# airButtonSwitch.net
KiCad netlist of a schematic drawn in EAGLE
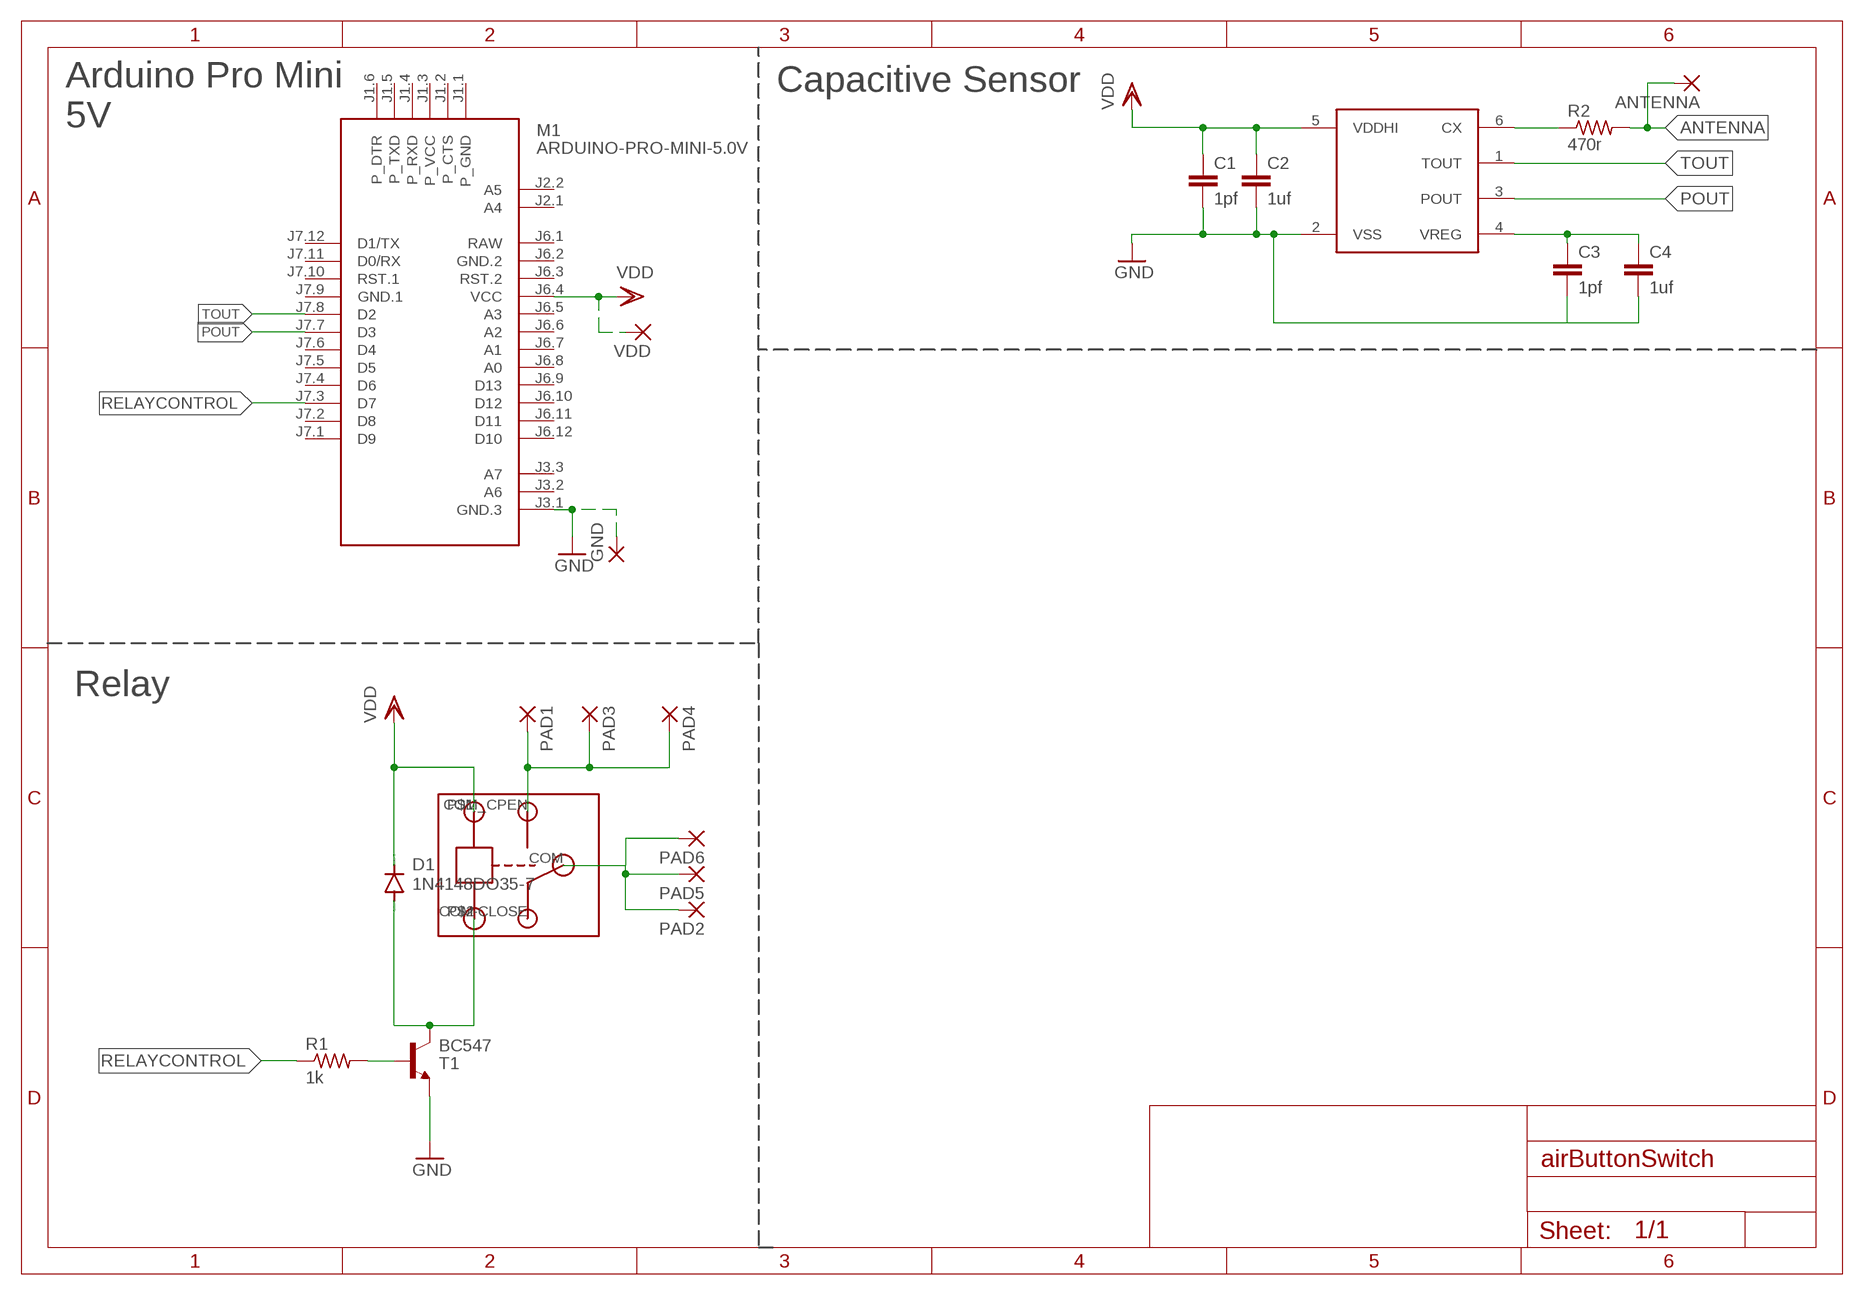
[diagram p0: schematic, sheet 1]

(export (version "E")
  (design (tool "Eeschema 10.0.6"))
  (components
    (comp (ref "ANTENNA")
      (value "2,54/1,0")
      (footprint "eagle-import:2,54_1,0")
      (libsource (lib "eagle-import") (part "2,54/1,0"))
    )
    (comp (ref "C1")
      (value "1pf")
      (footprint "eagle-import:C0805")
      (libsource (lib "eagle-import") (part "C-EUC0805"))
    )
    (comp (ref "C2")
      (value "1uf")
      (footprint "eagle-import:C0805")
      (libsource (lib "eagle-import") (part "C-EUC0805"))
    )
    (comp (ref "C3")
      (value "1pf")
      (footprint "eagle-import:C0805")
      (libsource (lib "eagle-import") (part "C-EUC0805"))
    )
    (comp (ref "C4")
      (value "1uf")
      (footprint "eagle-import:C0805")
      (libsource (lib "eagle-import") (part "C-EUC0805"))
    )
    (comp (ref "D1")
      (value "1N4148DO35-7")
      (footprint "eagle-import:DO35-7")
      (libsource (lib "eagle-import") (part "1N4148DO35-7"))
    )
    (comp (ref "GND")
      (value "2,54/1,0")
      (footprint "eagle-import:2,54_1,0")
      (libsource (lib "eagle-import") (part "2,54/1,0"))
    )
    (comp (ref "M1")
      (value "ARDUINO-PRO-MINI-5.0V")
      (footprint "eagle-import:ARDUINO-PRO-MINI")
      (libsource (lib "eagle-import") (part "ARDUINO-PRO-MINI-5.0V"))
    )
    (comp (ref "PAD1")
      (value "2,54/1,0")
      (footprint "eagle-import:2,54_1,0")
      (libsource (lib "eagle-import") (part "2,54/1,0"))
    )
    (comp (ref "PAD2")
      (value "2,54/1,0")
      (footprint "eagle-import:2,54_1,0")
      (libsource (lib "eagle-import") (part "2,54/1,0"))
    )
    (comp (ref "PAD3")
      (value "2,54/1,0")
      (footprint "eagle-import:2,54_1,0")
      (libsource (lib "eagle-import") (part "2,54/1,0"))
    )
    (comp (ref "PAD4")
      (value "2,54/1,0")
      (footprint "eagle-import:2,54_1,0")
      (libsource (lib "eagle-import") (part "2,54/1,0"))
    )
    (comp (ref "PAD5")
      (value "2,54/1,0")
      (footprint "eagle-import:2,54_1,0")
      (libsource (lib "eagle-import") (part "2,54/1,0"))
    )
    (comp (ref "PAD6")
      (value "2,54/1,0")
      (footprint "eagle-import:2,54_1,0")
      (libsource (lib "eagle-import") (part "2,54/1,0"))
    )
    (comp (ref "R1")
      (value "1k")
      (footprint "eagle-import:0309_10")
      (libsource (lib "eagle-import") (part "resistor_348_R-US_0309/10"))
    )
    (comp (ref "R2")
      (value "470r")
      (footprint "eagle-import:R0805")
      (libsource (lib "eagle-import") (part "R-US_R0805"))
    )
    (comp (ref "T1")
      (value "BC547")
      (footprint "eagle-import:TO92")
      (libsource (lib "eagle-import") (part "BC547"))
    )
    (comp (ref "U$1")
      (value "IQS127D")
      (footprint "eagle-import:SOT23-6")
      (libsource (lib "eagle-import") (part "IQS127D"))
    )
    (comp (ref "U$2")
      (value "RELAY")
      (footprint "eagle-import:RELAY")
      (libsource (lib "eagle-import") (part "RELAY"))
    )
    (comp (ref "VDD")
      (value "2,54/1,0")
      (footprint "eagle-import:2,54_1,0")
      (libsource (lib "eagle-import") (part "2,54/1,0"))
    )
  )
  (nets
    (net (code "1") (name "/GND.1") (class "Default")
      (node (ref "M1") (pin "J7.9") (pinfunction "GND.1_J7.9") (pintype "power_in"))
    )
    (net (code "2") (name "/GND.2") (class "Default")
      (node (ref "M1") (pin "J6.2") (pinfunction "GND.2_J6.2") (pintype "power_in"))
    )
    (net (code "3") (name "/RAW") (class "Default")
      (node (ref "M1") (pin "J6.1") (pinfunction "RAW_J6.1") (pintype "power_in"))
    )
    (net (code "4") (name "ANTENNA") (class "Default")
      (node (ref "ANTENNA") (pin "1") (pinfunction "P_1") (pintype "passive"))
      (node (ref "R2") (pin "2") (pinfunction "2_2") (pintype "passive"))
    )
    (net (code "5") (name "GND") (class "Default")
      (node (ref "C1") (pin "2") (pinfunction "2_2") (pintype "passive"))
      (node (ref "C2") (pin "2") (pinfunction "2_2") (pintype "passive"))
      (node (ref "C3") (pin "2") (pinfunction "2_2") (pintype "passive"))
      (node (ref "C4") (pin "2") (pinfunction "2_2") (pintype "passive"))
      (node (ref "GND") (pin "1") (pinfunction "P_1") (pintype "passive"))
      (node (ref "M1") (pin "J3.1") (pinfunction "GND.3_J3.1") (pintype "bidirectional"))
      (node (ref "T1") (pin "1") (pinfunction "E_1") (pintype "passive"))
      (node (ref "U$1") (pin "2") (pinfunction "VSS_2") (pintype "bidirectional"))
    )
    (net (code "6") (name "Net-(PAD1-P)") (class "Default")
      (node (ref "PAD1") (pin "1") (pinfunction "P_1") (pintype "passive"))
      (node (ref "PAD3") (pin "1") (pinfunction "P_1") (pintype "passive"))
      (node (ref "PAD4") (pin "1") (pinfunction "P_1") (pintype "passive"))
      (node (ref "U$2") (pin "COM_CPEN") (pinfunction "COM-OPEN_COM_CPEN") (pintype "bidirectional"))
    )
    (net (code "7") (name "Net-(PAD2-P)") (class "Default")
      (node (ref "PAD2") (pin "1") (pinfunction "P_1") (pintype "passive"))
      (node (ref "PAD5") (pin "1") (pinfunction "P_1") (pintype "passive"))
      (node (ref "PAD6") (pin "1") (pinfunction "P_1") (pintype "passive"))
      (node (ref "U$2") (pin "COM") (pinfunction "COM_COM") (pintype "bidirectional"))
    )
    (net (code "8") (name "Net-(T1-B)") (class "Default")
      (node (ref "R1") (pin "2") (pinfunction "2_2") (pintype "passive"))
      (node (ref "T1") (pin "2") (pinfunction "B_2") (pintype "passive"))
    )
    (net (code "9") (name "Net-(T1-C)") (class "Default")
      (node (ref "D1") (pin "A") (pinfunction "A_A") (pintype "passive"))
      (node (ref "T1") (pin "3") (pinfunction "C_3") (pintype "passive"))
      (node (ref "U$2") (pin "P$2") (pinfunction "GND_P$2") (pintype "bidirectional"))
    )
    (net (code "10") (name "Net-(U$1-CX)") (class "Default")
      (node (ref "R2") (pin "1") (pinfunction "1_1") (pintype "passive"))
      (node (ref "U$1") (pin "6") (pinfunction "CX_6") (pintype "bidirectional"))
    )
    (net (code "11") (name "Net-(U$1-VREG)") (class "Default")
      (node (ref "C3") (pin "1") (pinfunction "1_1") (pintype "passive"))
      (node (ref "C4") (pin "1") (pinfunction "1_1") (pintype "passive"))
      (node (ref "U$1") (pin "4") (pinfunction "VREG_4") (pintype "bidirectional"))
    )
    (net (code "12") (name "POUT") (class "Default")
      (node (ref "M1") (pin "J7.7") (pinfunction "D3_J7.7") (pintype "bidirectional"))
      (node (ref "U$1") (pin "3") (pinfunction "POUT_3") (pintype "bidirectional"))
    )
    (net (code "13") (name "RELAYCONTROL") (class "Default")
      (node (ref "M1") (pin "J7.3") (pinfunction "D7_J7.3") (pintype "bidirectional"))
      (node (ref "R1") (pin "1") (pinfunction "1_1") (pintype "passive"))
    )
    (net (code "14") (name "TOUT") (class "Default")
      (node (ref "M1") (pin "J7.8") (pinfunction "D2_J7.8") (pintype "bidirectional"))
      (node (ref "U$1") (pin "1") (pinfunction "TOUT_1") (pintype "bidirectional"))
    )
    (net (code "15") (name "VDD") (class "Default")
      (node (ref "C1") (pin "1") (pinfunction "1_1") (pintype "passive"))
      (node (ref "C2") (pin "1") (pinfunction "1_1") (pintype "passive"))
      (node (ref "D1") (pin "C") (pinfunction "C_C") (pintype "passive"))
      (node (ref "M1") (pin "J6.4") (pinfunction "VCC_J6.4") (pintype "power_in"))
      (node (ref "U$1") (pin "5") (pinfunction "VDDHI_5") (pintype "bidirectional"))
      (node (ref "U$2") (pin "P$1") (pinfunction "IN_P$1") (pintype "bidirectional"))
      (node (ref "VDD") (pin "1") (pinfunction "P_1") (pintype "passive"))
    )
    (net (code "16") (name "unconnected-(M1-A0-PadJ6.8)") (class "Default")
      (node (ref "M1") (pin "J6.8") (pinfunction "A0_J6.8") (pintype "bidirectional"))
    )
    (net (code "17") (name "unconnected-(M1-A1-PadJ6.7)") (class "Default")
      (node (ref "M1") (pin "J6.7") (pinfunction "A1_J6.7") (pintype "bidirectional"))
    )
    (net (code "18") (name "unconnected-(M1-A2-PadJ6.6)") (class "Default")
      (node (ref "M1") (pin "J6.6") (pinfunction "A2_J6.6") (pintype "bidirectional"))
    )
    (net (code "19") (name "unconnected-(M1-A3-PadJ6.5)") (class "Default")
      (node (ref "M1") (pin "J6.5") (pinfunction "A3_J6.5") (pintype "bidirectional"))
    )
    (net (code "20") (name "unconnected-(M1-A4-PadJ2.1)") (class "Default")
      (node (ref "M1") (pin "J2.1") (pinfunction "A4_J2.1") (pintype "bidirectional"))
    )
    (net (code "21") (name "unconnected-(M1-A5-PadJ2.2)") (class "Default")
      (node (ref "M1") (pin "J2.2") (pinfunction "A5_J2.2") (pintype "bidirectional"))
    )
    (net (code "22") (name "unconnected-(M1-A6-PadJ3.2)") (class "Default")
      (node (ref "M1") (pin "J3.2") (pinfunction "A6_J3.2") (pintype "bidirectional"))
    )
    (net (code "23") (name "unconnected-(M1-A7-PadJ3.3)") (class "Default")
      (node (ref "M1") (pin "J3.3") (pinfunction "A7_J3.3") (pintype "bidirectional"))
    )
    (net (code "24") (name "unconnected-(M1-D0{slash}RX-PadJ7.11)") (class "Default")
      (node (ref "M1") (pin "J7.11") (pinfunction "D0/RX_J7.11") (pintype "bidirectional"))
    )
    (net (code "25") (name "unconnected-(M1-D1{slash}TX-PadJ7.12)") (class "Default")
      (node (ref "M1") (pin "J7.12") (pinfunction "D1/TX_J7.12") (pintype "bidirectional"))
    )
    (net (code "26") (name "unconnected-(M1-D4-PadJ7.6)") (class "Default")
      (node (ref "M1") (pin "J7.6") (pinfunction "D4_J7.6") (pintype "bidirectional"))
    )
    (net (code "27") (name "unconnected-(M1-D5-PadJ7.5)") (class "Default")
      (node (ref "M1") (pin "J7.5") (pinfunction "D5_J7.5") (pintype "bidirectional"))
    )
    (net (code "28") (name "unconnected-(M1-D6-PadJ7.4)") (class "Default")
      (node (ref "M1") (pin "J7.4") (pinfunction "D6_J7.4") (pintype "bidirectional"))
    )
    (net (code "29") (name "unconnected-(M1-D8-PadJ7.2)") (class "Default")
      (node (ref "M1") (pin "J7.2") (pinfunction "D8_J7.2") (pintype "bidirectional"))
    )
    (net (code "30") (name "unconnected-(M1-D9-PadJ7.1)") (class "Default")
      (node (ref "M1") (pin "J7.1") (pinfunction "D9_J7.1") (pintype "bidirectional"))
    )
    (net (code "31") (name "unconnected-(M1-D10-PadJ6.12)") (class "Default")
      (node (ref "M1") (pin "J6.12") (pinfunction "D10_J6.12") (pintype "bidirectional"))
    )
    (net (code "32") (name "unconnected-(M1-D11-PadJ6.11)") (class "Default")
      (node (ref "M1") (pin "J6.11") (pinfunction "D11_J6.11") (pintype "bidirectional"))
    )
    (net (code "33") (name "unconnected-(M1-D12-PadJ6.10)") (class "Default")
      (node (ref "M1") (pin "J6.10") (pinfunction "D12_J6.10") (pintype "bidirectional"))
    )
    (net (code "34") (name "unconnected-(M1-D13-PadJ6.9)") (class "Default")
      (node (ref "M1") (pin "J6.9") (pinfunction "D13_J6.9") (pintype "bidirectional"))
    )
    (net (code "35") (name "unconnected-(M1-P_CTS-PadJ1.2)") (class "Default")
      (node (ref "M1") (pin "J1.2") (pinfunction "P_CTS_J1.2") (pintype "bidirectional"))
    )
    (net (code "36") (name "unconnected-(M1-P_DTR-PadJ1.6)") (class "Default")
      (node (ref "M1") (pin "J1.6") (pinfunction "P_DTR_J1.6") (pintype "bidirectional"))
    )
    (net (code "37") (name "unconnected-(M1-P_GND-PadJ1.1)") (class "Default")
      (node (ref "M1") (pin "J1.1") (pinfunction "P_GND_J1.1") (pintype "bidirectional"))
    )
    (net (code "38") (name "unconnected-(M1-P_RXD-PadJ1.4)") (class "Default")
      (node (ref "M1") (pin "J1.4") (pinfunction "P_RXD_J1.4") (pintype "bidirectional"))
    )
    (net (code "39") (name "unconnected-(M1-P_TXD-PadJ1.5)") (class "Default")
      (node (ref "M1") (pin "J1.5") (pinfunction "P_TXD_J1.5") (pintype "bidirectional"))
    )
    (net (code "40") (name "unconnected-(M1-P_VCC-PadJ1.3)") (class "Default")
      (node (ref "M1") (pin "J1.3") (pinfunction "P_VCC_J1.3") (pintype "bidirectional"))
    )
    (net (code "41") (name "unconnected-(M1-RST.1-PadJ7.10)") (class "Default")
      (node (ref "M1") (pin "J7.10") (pinfunction "RST.1_J7.10") (pintype "bidirectional"))
    )
    (net (code "42") (name "unconnected-(M1-RST.2-PadJ6.3)") (class "Default")
      (node (ref "M1") (pin "J6.3") (pinfunction "RST.2_J6.3") (pintype "bidirectional"))
    )
    (net (code "43") (name "unconnected-(U$2-PadCOM-CLOSE)") (class "Default")
      (node (ref "U$2") (pin "COM-CLOSE") (pinfunction "COM-CLOSE_COM-CLOSE") (pintype "bidirectional"))
    )
  )
)
